# I2C_Buffer.net
KiCad netlist of a schematic drawn in Altium Designer
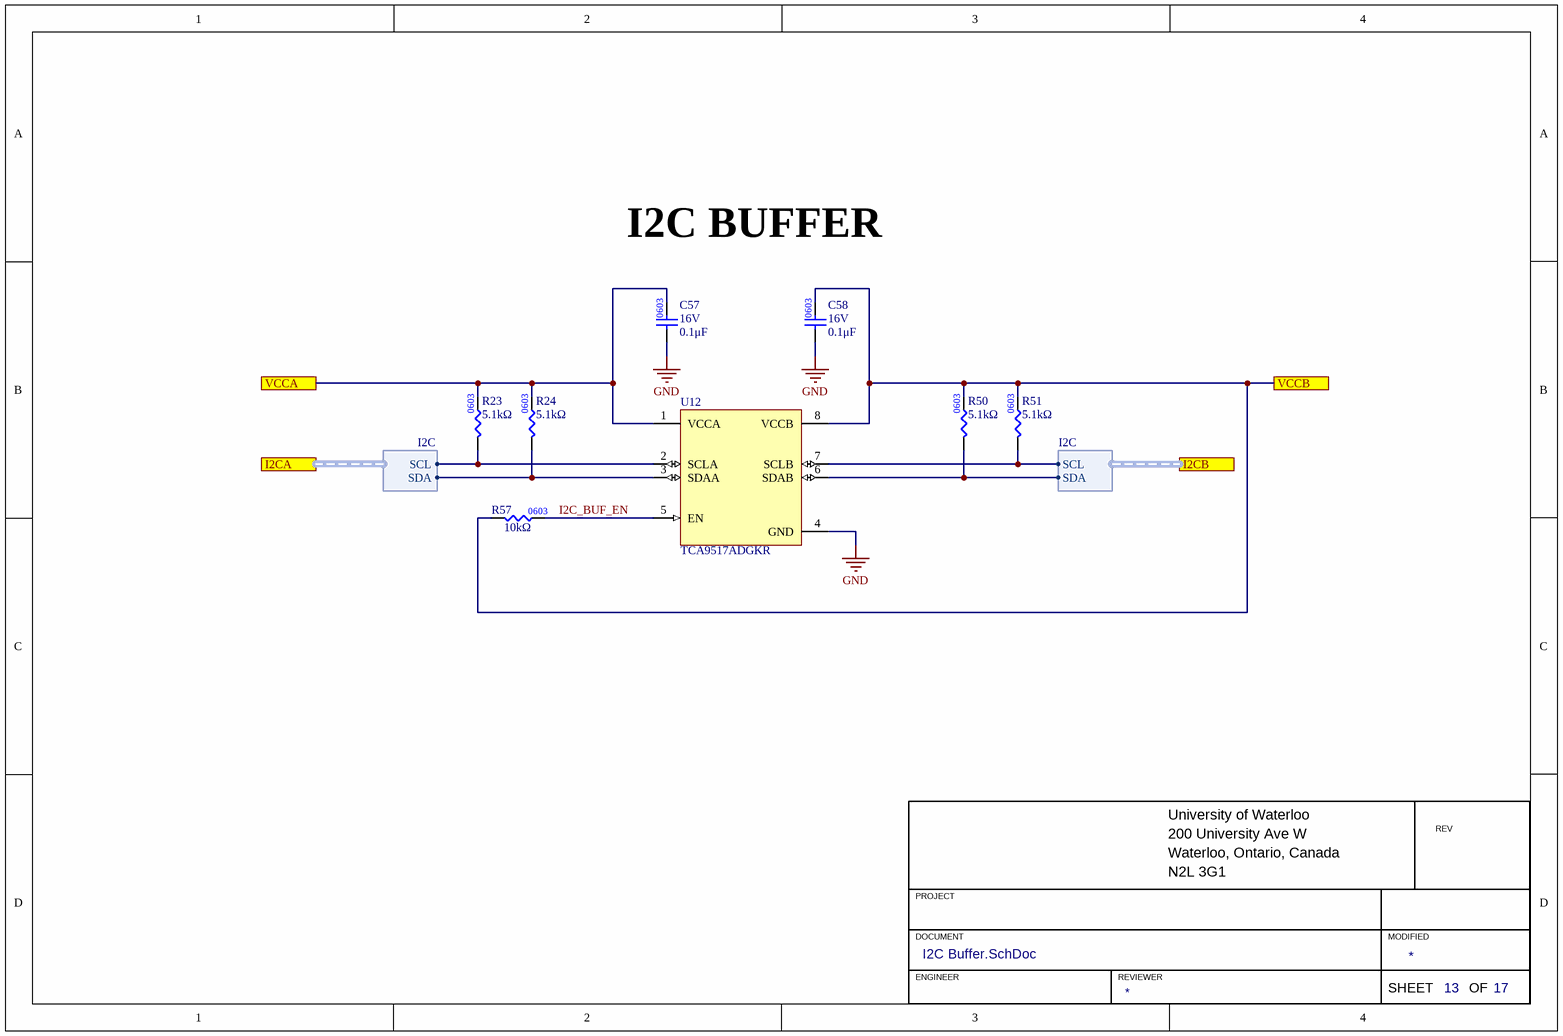
[diagram p0: I2C Buffer.SchDoc]

(export (version "E")
  (design (tool "Eeschema 10.0.6"))
  (components
    (comp (ref "C57")
      (value "0.1μF")
      (footprint "CAP0603")
      (description "CAP CER 0.1UF 16V X7R 0603")
      (fields (field (name "VOLTAGE RATING") "16V") (field (name "Comment") "CAP_0.1uF_16V_0603"))
      (libsource (lib "Personal_Schematic_Library_2022") (part "CAP_0.1uF_16V_0603"))
    )
    (comp (ref "C58")
      (value "0.1μF")
      (footprint "CAP0603")
      (description "CAP CER 0.1UF 16V X7R 0603")
      (fields (field (name "VOLTAGE RATING") "16V") (field (name "Comment") "CAP_0.1uF_16V_0603"))
      (libsource (lib "Personal_Schematic_Library_2022") (part "CAP_0.1uF_16V_0603"))
    )
    (comp (ref "R23")
      (value "5.1kΩ")
      (footprint "RES0603")
      (description "RES 5.1K OHM 1% 1/10W 0603")
      (fields (field (name "Comment") "RES_5.1kΩ_0603_1%"))
      (libsource (lib "Personal_Schematic_Library_2022") (part "RES_5.1kΩ_0603_1%"))
    )
    (comp (ref "R24")
      (value "5.1kΩ")
      (footprint "RES0603")
      (description "RES 5.1K OHM 1% 1/10W 0603")
      (fields (field (name "Comment") "RES_5.1kΩ_0603_1%"))
      (libsource (lib "Personal_Schematic_Library_2022") (part "RES_5.1kΩ_0603_1%"))
    )
    (comp (ref "R50")
      (value "5.1kΩ")
      (footprint "RES0603")
      (description "RES 5.1K OHM 1% 1/10W 0603")
      (fields (field (name "Comment") "RES_5.1kΩ_0603_1%"))
      (libsource (lib "Personal_Schematic_Library_2022") (part "RES_5.1kΩ_0603_1%"))
    )
    (comp (ref "R51")
      (value "5.1kΩ")
      (footprint "RES0603")
      (description "RES 5.1K OHM 1% 1/10W 0603")
      (fields (field (name "Comment") "RES_5.1kΩ_0603_1%"))
      (libsource (lib "Personal_Schematic_Library_2022") (part "RES_5.1kΩ_0603_1%"))
    )
    (comp (ref "R57")
      (value "10kΩ")
      (footprint "RES0603")
      (description "RES 10K OHM 1% 1/8W 0603")
      (fields (field (name "Comment") "RES_10kΩ_0603_1%"))
      (libsource (lib "Personal_Schematic_Library_2022") (part "RES_10kΩ_0603_1%"))
    )
    (comp (ref "U12")
      (value "TCA9517ADGKR")
      (footprint "TI_8-VSSOP")
      (description "IC XLTR VL BIDIR 8-VSSOP")
      (libsource (lib "Personal_Schematic_Library_2022") (part "TCA9517ADGKR"))
    )
  )
  (nets
    (net (code "2") (name "/I2C_BUF_EN") (class "Default")
      (node (ref "R57") (pin "2") (pinfunction "2_2") (pintype "passive"))
      (node (ref "U12") (pin "5") (pinfunction "EN_5") (pintype "input"))
    )
    (net (code "3") (name "/VCCA") (class "Default")
      (node (ref "C57") (pin "2") (pinfunction "2_2") (pintype "passive"))
      (node (ref "R23") (pin "2") (pinfunction "2_2") (pintype "passive"))
      (node (ref "R24") (pin "2") (pinfunction "2_2") (pintype "passive"))
      (node (ref "U12") (pin "1") (pinfunction "VCCA_1") (pintype "power_in"))
    )
    (net (code "4") (name "/VCCB") (class "Default")
      (node (ref "C58") (pin "2") (pinfunction "2_2") (pintype "passive"))
      (node (ref "R50") (pin "2") (pinfunction "2_2") (pintype "passive"))
      (node (ref "R51") (pin "2") (pinfunction "2_2") (pintype "passive"))
      (node (ref "R57") (pin "1") (pinfunction "1_1") (pintype "passive"))
      (node (ref "U12") (pin "8") (pinfunction "VCCB_8") (pintype "power_in"))
    )
    (net (code "6") (name "GND") (class "Default")
      (node (ref "C57") (pin "1") (pinfunction "1_1") (pintype "passive"))
      (node (ref "C58") (pin "1") (pinfunction "1_1") (pintype "passive"))
      (node (ref "U12") (pin "4") (pinfunction "GND_4") (pintype "power_in"))
    )
    (net (code "7") (name "Net-(U12-SCLA)") (class "Default")
      (node (ref "R23") (pin "1") (pinfunction "1_1") (pintype "passive"))
      (node (ref "U12") (pin "2") (pinfunction "SCLA_2") (pintype "bidirectional"))
    )
    (net (code "8") (name "Net-(U12-SCLB)") (class "Default")
      (node (ref "R51") (pin "1") (pinfunction "1_1") (pintype "passive"))
      (node (ref "U12") (pin "7") (pinfunction "SCLB_7") (pintype "bidirectional"))
    )
    (net (code "9") (name "Net-(U12-SDAA)") (class "Default")
      (node (ref "R24") (pin "1") (pinfunction "1_1") (pintype "passive"))
      (node (ref "U12") (pin "3") (pinfunction "SDAA_3") (pintype "bidirectional"))
    )
    (net (code "10") (name "Net-(U12-SDAB)") (class "Default")
      (node (ref "R50") (pin "1") (pinfunction "1_1") (pintype "passive"))
      (node (ref "U12") (pin "6") (pinfunction "SDAB_6") (pintype "bidirectional"))
    )
  )
)
